# ProProject_stm32_motordrive_2024-05-07.net
KiCad netlist of a schematic drawn in EasyEDA Pro
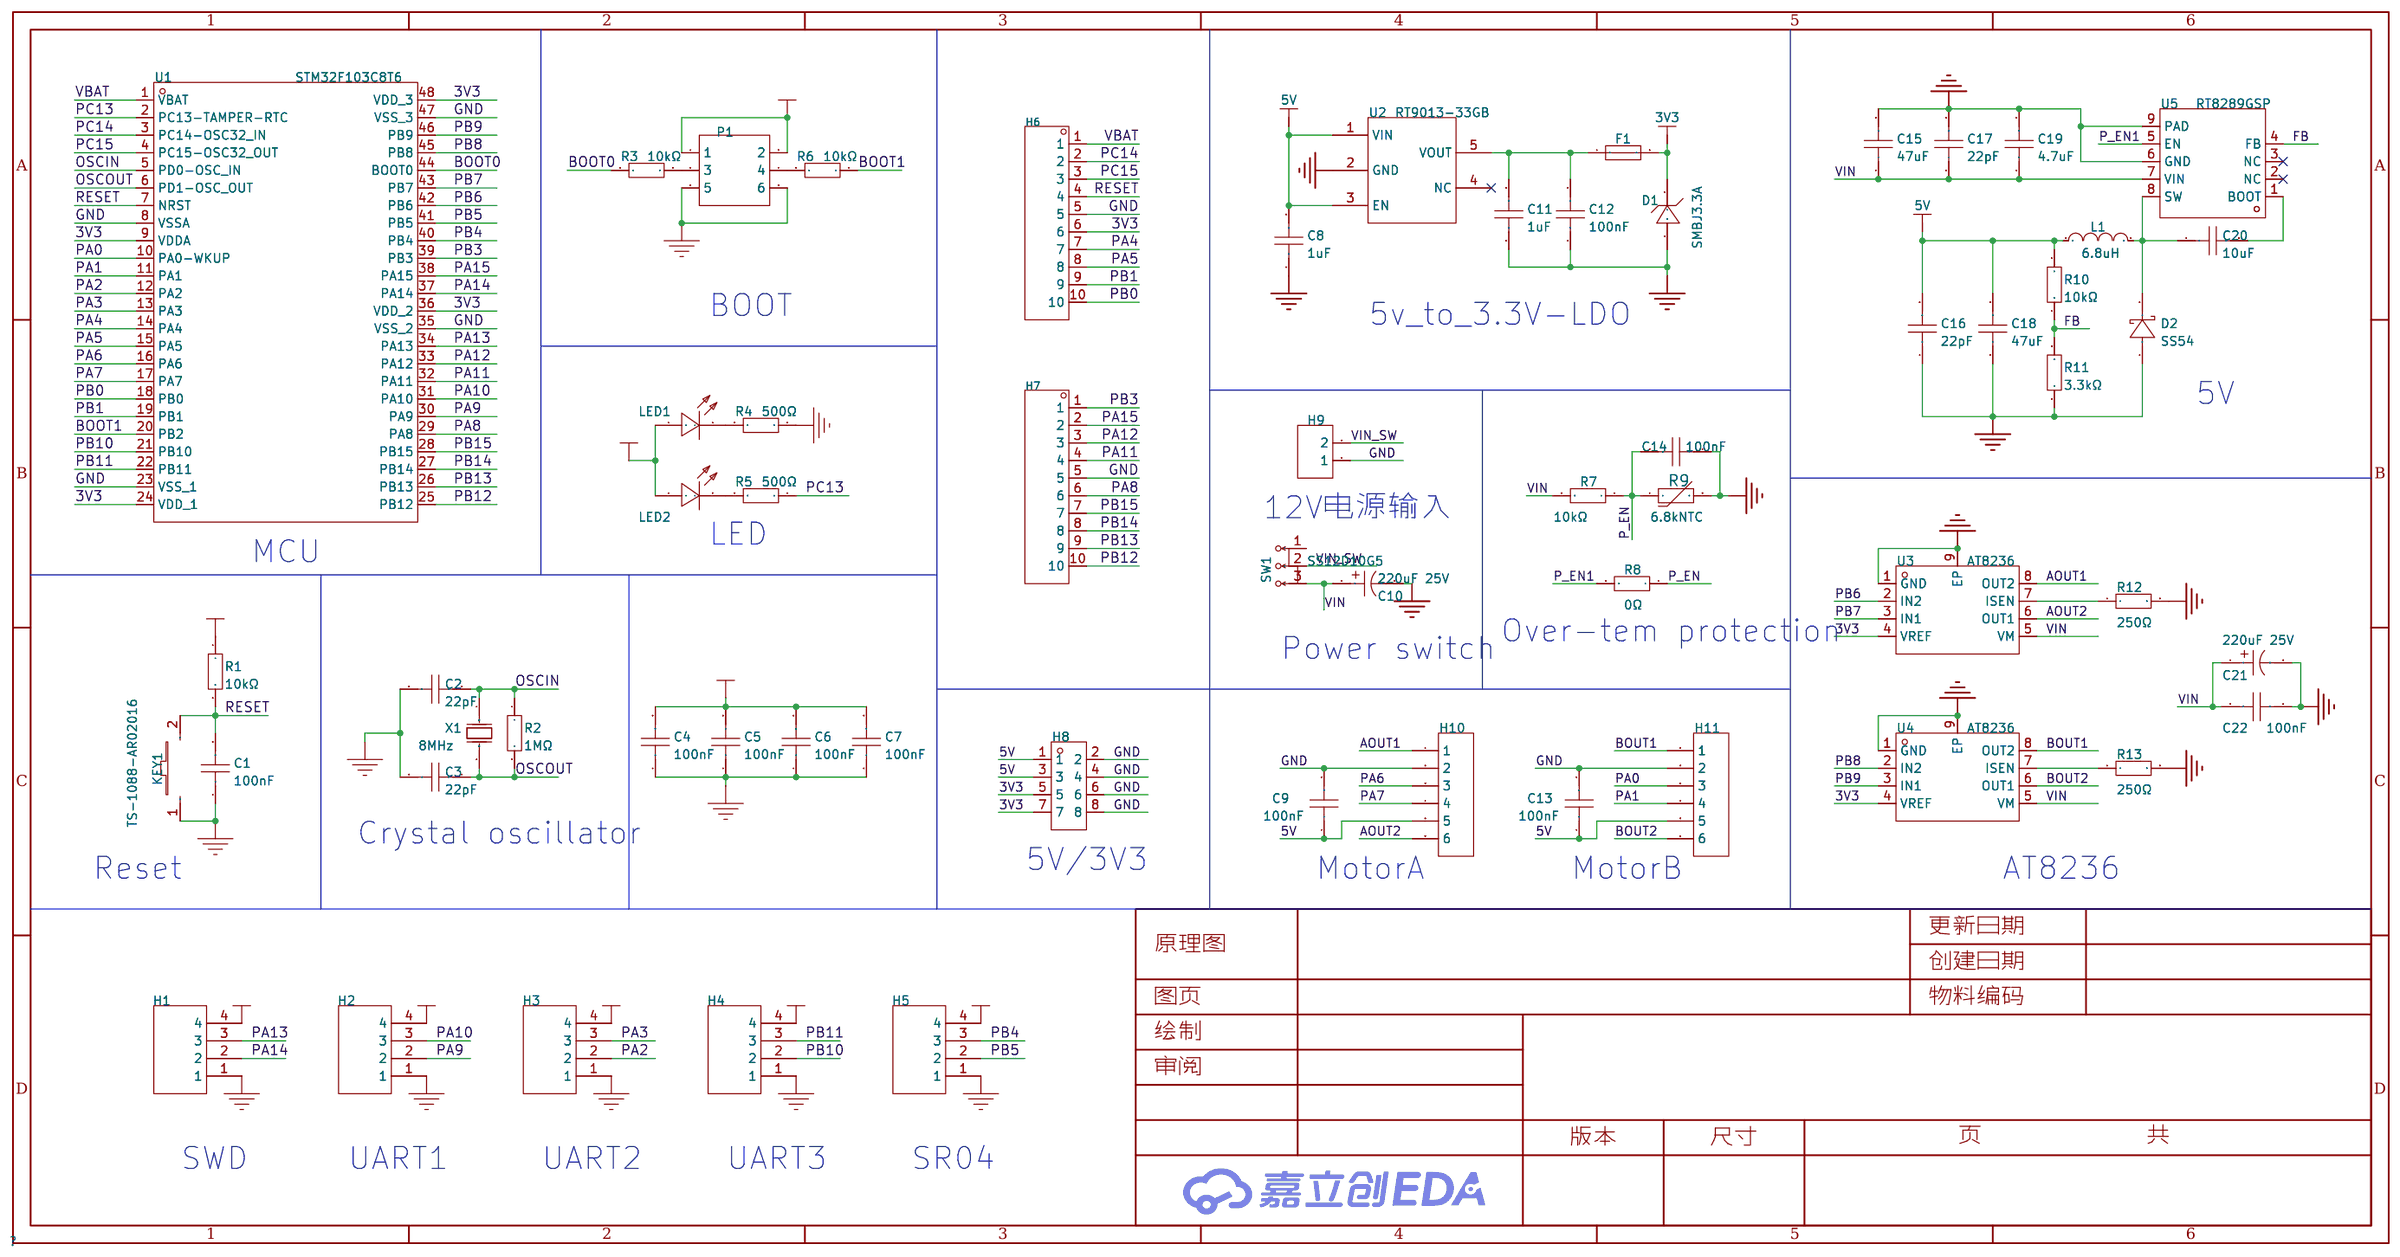
[diagram p0: schematic sheet]

(export (version "E")
  (design (tool "Eeschema 10.0.6"))
  (components
    (comp (ref "C1")
      (value "100nF")
      (fields
        (field (name "Manufacturer Part") "CC0603KRX7R9BB104")
        (field (name "Manufacturer") "YAGEO(国巨)")
      )
      (libsource (lib "easyedapro") (part "104"))
    )
    (comp (ref "C2")
      (value "22pF")
      (fields
        (field (name "Manufacturer Part") "CC0603JRNPO9BN220")
        (field (name "Manufacturer") "YAGEO(国巨)")
      )
      (libsource (lib "easyedapro") (part "22P"))
    )
    (comp (ref "C3")
      (value "22pF")
      (fields
        (field (name "Manufacturer Part") "CC0603JRNPO9BN220")
        (field (name "Manufacturer") "YAGEO(国巨)")
      )
      (libsource (lib "easyedapro") (part "22P"))
    )
    (comp (ref "C4")
      (value "100nF")
      (fields
        (field (name "Manufacturer Part") "CC0603KRX7R9BB104")
        (field (name "Manufacturer") "YAGEO(国巨)")
      )
      (libsource (lib "easyedapro") (part "104"))
    )
    (comp (ref "C5")
      (value "100nF")
      (fields
        (field (name "Manufacturer Part") "CC0603KRX7R9BB104")
        (field (name "Manufacturer") "YAGEO(国巨)")
      )
      (libsource (lib "easyedapro") (part "104"))
    )
    (comp (ref "C6")
      (value "100nF")
      (fields
        (field (name "Manufacturer Part") "CC0603KRX7R9BB104")
        (field (name "Manufacturer") "YAGEO(国巨)")
      )
      (libsource (lib "easyedapro") (part "104"))
    )
    (comp (ref "C7")
      (value "100nF")
      (fields
        (field (name "Manufacturer Part") "CC0603KRX7R9BB104")
        (field (name "Manufacturer") "YAGEO(国巨)")
      )
      (libsource (lib "easyedapro") (part "104"))
    )
    (comp (ref "C8")
      (value "1uF")
      (fields
        (field (name "Manufacturer Part") "CL10A105KB8NNNC")
        (field (name "Manufacturer") "SAMSUNG(三星)")
      )
      (libsource (lib "easyedapro") (part "CapAcitance"))
    )
    (comp (ref "C9")
      (value "100nF")
      (fields
        (field (name "Manufacturer Part") "CC0603KRX7R9BB104")
        (field (name "Manufacturer") "YAGEO(国巨)")
      )
      (libsource (lib "easyedapro") (part "CapAcitance"))
    )
    (comp (ref "C10")
      (value "220uF 25V")
      (footprint "easyedapro:CAP-SMD_BD6.3-L6.6-W6.6-LS7.2-FD")
      (description "容值:220uF;精度:±20%;额定电压:25V;纹波电流:165mA@120Hz;等效串联电阻:-;")
      (fields (field (name "Manufacturer Part") "RST220UF25V019") (field (name "Manufacturer") "KNSCHA(科尼盛)"))
      (libsource (lib "easyedapro") (part "RST220UF25V019"))
    )
    (comp (ref "C11")
      (value "1uF")
      (fields
        (field (name "Manufacturer Part") "CL10A105KB8NNNC")
        (field (name "Manufacturer") "SAMSUNG(三星)")
      )
      (libsource (lib "easyedapro") (part "CapAcitance"))
    )
    (comp (ref "C12")
      (value "100nF")
      (fields
        (field (name "Manufacturer Part") "CC0603KRX7R9BB104")
        (field (name "Manufacturer") "YAGEO(国巨)")
      )
      (libsource (lib "easyedapro") (part "CapAcitance"))
    )
    (comp (ref "C13")
      (value "100nF")
      (fields
        (field (name "Manufacturer Part") "CC0603KRX7R9BB104")
        (field (name "Manufacturer") "YAGEO(国巨)")
      )
      (libsource (lib "easyedapro") (part "CapAcitance"))
    )
    (comp (ref "C14")
      (value "100nF")
      (fields
        (field (name "Manufacturer Part") "CC0603KRX7R9BB104")
        (field (name "Manufacturer") "YAGEO(国巨)")
      )
      (libsource (lib "easyedapro") (part "CapAcitance"))
    )
    (comp (ref "C15")
      (value "47uF")
      (fields
        (field (name "Manufacturer Part") "CL10A476MQ8QRNC")
        (field (name "Manufacturer") "SAMSUNG(三星)")
      )
      (libsource (lib "easyedapro") (part "CapAcitance"))
    )
    (comp (ref "C16")
      (value "22pF")
      (fields
        (field (name "Manufacturer Part") "CC0603JRNPO9BN220")
        (field (name "Manufacturer") "YAGEO(国巨)")
      )
      (libsource (lib "easyedapro") (part "CapAcitance"))
    )
    (comp (ref "C17")
      (value "22pF")
      (fields
        (field (name "Manufacturer Part") "CC0603JRNPO9BN220")
        (field (name "Manufacturer") "YAGEO(国巨)")
      )
      (libsource (lib "easyedapro") (part "CapAcitance"))
    )
    (comp (ref "C18")
      (value "47uF")
      (fields
        (field (name "Manufacturer Part") "CL10A476MQ8QRNC")
        (field (name "Manufacturer") "SAMSUNG(三星)")
      )
      (libsource (lib "easyedapro") (part "CapAcitance"))
    )
    (comp (ref "C19")
      (value "4.7uF")
      (fields
        (field (name "Manufacturer Part") "CL10A475KP8NNNC")
        (field (name "Manufacturer") "SAMSUNG(三星)")
      )
      (libsource (lib "easyedapro") (part "CapAcitance"))
    )
    (comp (ref "C20")
      (value "10uF")
      (fields
        (field (name "Manufacturer Part") "CL10A106KP8NNNC")
        (field (name "Manufacturer") "SAMSUNG(三星)")
      )
      (libsource (lib "easyedapro") (part "CapAcitance"))
    )
    (comp (ref "C21")
      (value "220uF 25V")
      (footprint "easyedapro:CAP-SMD_BD6.3-L6.6-W6.6-LS7.2-FD")
      (description "容值:220uF;精度:±20%;额定电压:25V;纹波电流:165mA@120Hz;等效串联电阻:-;")
      (fields (field (name "Manufacturer Part") "RST220UF25V019") (field (name "Manufacturer") "KNSCHA(科尼盛)"))
      (libsource (lib "easyedapro") (part "RST220UF25V019"))
    )
    (comp (ref "C22")
      (value "100nF")
      (fields
        (field (name "Manufacturer Part") "CC0603KRX7R9BB104")
        (field (name "Manufacturer") "YAGEO(国巨)")
      )
      (libsource (lib "easyedapro") (part "CapAcitance"))
    )
    (comp (ref "D1")
      (value "SMBJ3.3A")
      (footprint "easyedapro:SMB_L4.6-W3.6-LS5.3-RD")
      (description "反向截止电压(Vrwm):3.3V;最大钳位电压:7.3V;峰值脉冲功率(Ppp)@10/1000us:600W;击穿电压:4.1V;")
      (fields (field (name "Manufacturer") "JKSEMI(金开盛)"))
      (libsource (lib "easyedapro") (part "SMBJ3.3A_C362089"))
    )
    (comp (ref "D2")
      (value "SS54")
      (footprint "easyedapro:SMA_L4.3-W2.6-LS5.0-FD")
      (description "二极管配置:独立式;正向压降(Vf):550mV@5.0A;直流反向耐压(Vr):40V;平均整流电流(Io):5A;")
      (fields (field (name "Manufacturer") "宏迦橙"))
      (libsource (lib "easyedapro") (part "SS54_C7420369"))
    )
    (comp (ref "F1")
      (value "BSMD0603-050-6V")
      (footprint "easyedapro:F0603")
      (description "最大电压:6V;最大电流:40A;保持电流:500mA;跳闸电流:1A;")
      (fields (field (name "Manufacturer") "BHFUSE(佰宏)"))
      (libsource (lib "easyedapro") (part "BSMD0603-050-6V"))
    )
    (comp (ref "H1")
      (value "PZ254V-11-04P")
      (fields (field (name "Manufacturer") "XFCN(兴飞)"))
      (libsource (lib "easyedapro") (part "220S-1*4P H=8.5MM Ytype Gold-plated"))
    )
    (comp (ref "H2")
      (value "PZ254V-11-04P")
      (fields (field (name "Manufacturer") "XFCN(兴飞)"))
      (libsource (lib "easyedapro") (part "220S-1*4P H=8.5MM Ytype Gold-plated"))
    )
    (comp (ref "H3")
      (value "PZ254V-11-04P")
      (fields (field (name "Manufacturer") "XFCN(兴飞)"))
      (libsource (lib "easyedapro") (part "220S-1*4P H=8.5MM Ytype Gold-plated"))
    )
    (comp (ref "H4")
      (value "PZ254V-11-04P")
      (fields (field (name "Manufacturer") "XFCN(兴飞)"))
      (libsource (lib "easyedapro") (part "220S-1*4P H=8.5MM Ytype Gold-plated"))
    )
    (comp (ref "H5")
      (value "PZ254V-11-04P")
      (fields (field (name "Manufacturer") "XFCN(兴飞)"))
      (libsource (lib "easyedapro") (part "220S-1*4P H=8.5MM Ytype Gold-plated"))
    )
    (comp (ref "H6")
      (value "2.54-1*10P针")
      (footprint "easyedapro:HDR-TH_10P-P2.54-V-M-1")
      (fields (field (name "Manufacturer") "BOOMELE(博穆精密)"))
      (libsource (lib "easyedapro") (part "Header-Male-2.54_1x10"))
    )
    (comp (ref "H7")
      (value "2.54-1*10P针")
      (footprint "easyedapro:HDR-TH_10P-P2.54-V-M-1")
      (fields (field (name "Manufacturer") "BOOMELE(博穆精密)"))
      (libsource (lib "easyedapro") (part "Header-Male-2.54_1x10"))
    )
    (comp (ref "H8")
      (value "PZ2.54-2*4")
      (footprint "easyedapro:HDR-TH_8P-P2.54-V-M-R2-C4-S2.54")
      (description "插针结构:2x4P;间距:2.54mm;排数:双排;总PIN位数:8P;")
      (fields (field (name "Manufacturer") "ZHOURI(洲日)"))
      (libsource (lib "easyedapro") (part "PZ2.54-2*4"))
    )
    (comp (ref "H9")
      (value "XY301V-A-5.0-2P")
      (fields (field (name "Manufacturer") "XINLAIYA(新莱亚)"))
      (libsource (lib "easyedapro") (part "Header-Female-2.54_1x2"))
    )
    (comp (ref "H10")
      (value "~")
      (footprint "easyedapro:XH2.54-LI-6P弯针")
      (libsource (lib "easyedapro") (part "XH2.54-LI-6P弯针"))
    )
    (comp (ref "H11")
      (value "~")
      (footprint "easyedapro:XH2.54-LI-6P弯针")
      (libsource (lib "easyedapro") (part "XH2.54-LI-6P弯针"))
    )
    (comp (ref "KEY1")
      (value "TS-1088-AR02016")
      (fields (field (name "Manufacturer") "XUNPU(讯普)"))
      (libsource (lib "easyedapro") (part "Switch3x4x2"))
    )
    (comp (ref "L1")
      (value "6.8uH")
      (fields (field (name "Manufacturer Part") "FXL0630-6R8-M") (field (name "Manufacturer") "cjiang(长江微电)"))
      (libsource (lib "easyedapro") (part "SDFL1608S100KTF"))
    )
    (comp (ref "LED1")
      (value "NCD0805R1")
      (fields (field (name "Manufacturer") "国星光电"))
      (libsource (lib "easyedapro") (part "204-10SURD/S530-A3"))
    )
    (comp (ref "LED2")
      (value "NCD0805R1")
      (fields (field (name "Manufacturer") "国星光电"))
      (libsource (lib "easyedapro") (part "204-10SURD/S530-A3"))
    )
    (comp (ref "P1")
      (value "2.54-2*3P针")
      (fields (field (name "Manufacturer") "BOOMELE(博穆精密)"))
      (libsource (lib "easyedapro") (part "HDR-IDC-2.54-2X3P"))
    )
    (comp (ref "R1")
      (value "10kΩ")
      (fields
        (field (name "Manufacturer Part") "0603WAF1002T5E")
        (field (name "Manufacturer") "UNI-ROYAL(厚声)")
      )
      (libsource (lib "easyedapro") (part "电阻"))
    )
    (comp (ref "R2")
      (value "1MΩ")
      (fields
        (field (name "Manufacturer Part") "0603WAF1004T5E")
        (field (name "Manufacturer") "UNI-ROYAL(厚声)")
      )
      (libsource (lib "easyedapro") (part "电阻"))
    )
    (comp (ref "R3")
      (value "10kΩ")
      (fields
        (field (name "Manufacturer Part") "0603WAF1002T5E")
        (field (name "Manufacturer") "UNI-ROYAL(厚声)")
      )
      (libsource (lib "easyedapro") (part "电阻"))
    )
    (comp (ref "R4")
      (value "500Ω")
      (fields (field (name "Manufacturer Part") "RT0603BRC07500RL") (field (name "Manufacturer") "YAGEO(国巨)"))
      (libsource (lib "easyedapro") (part "电阻"))
    )
    (comp (ref "R5")
      (value "500Ω")
      (fields (field (name "Manufacturer Part") "RT0603BRC07500RL") (field (name "Manufacturer") "YAGEO(国巨)"))
      (libsource (lib "easyedapro") (part "电阻"))
    )
    (comp (ref "R6")
      (value "10kΩ")
      (fields
        (field (name "Manufacturer Part") "0603WAF1002T5E")
        (field (name "Manufacturer") "UNI-ROYAL(厚声)")
      )
      (libsource (lib "easyedapro") (part "电阻"))
    )
    (comp (ref "R7")
      (value "10kΩ")
      (fields (field (name "Manufacturer Part") "RT0603BRD0710KL") (field (name "Manufacturer") "YAGEO(国巨)"))
      (libsource (lib "easyedapro") (part "电阻"))
    )
    (comp (ref "R8")
      (value "0Ω")
      (fields
        (field (name "Manufacturer Part") "0603WAF0000T5E")
        (field (name "Manufacturer") "UNI-ROYAL(厚声)")
      )
      (libsource (lib "easyedapro") (part "电阻"))
    )
    (comp (ref "R9")
      (value "6.8kNTC")
      (footprint "easyedapro:R0603")
      (description "阻值(25°C):6.8kΩ;B值(25°C/50°C):3950K;电阻精度:±5%;功率:100mW;B值精度:±3%;最大稳态电流(25°C):380uA;")
      (fields (field (name "Manufacturer") "muRata(村田)"))
      (libsource (lib "easyedapro") (part "NCP18XW682J03RB"))
    )
    (comp (ref "R10")
      (value "10kΩ")
      (fields (field (name "Manufacturer Part") "RT0603BRD0710KL") (field (name "Manufacturer") "YAGEO(国巨)"))
      (libsource (lib "easyedapro") (part "电阻"))
    )
    (comp (ref "R11")
      (value "3.3kΩ")
      (fields
        (field (name "Manufacturer Part") "0603WAF3301T5E")
        (field (name "Manufacturer") "UNI-ROYAL(厚声)")
      )
      (libsource (lib "easyedapro") (part "电阻"))
    )
    (comp (ref "R12")
      (value "250Ω")
      (fields (field (name "Manufacturer Part") "RT0603BRE07250RL") (field (name "Manufacturer") "YAGEO(国巨)"))
      (libsource (lib "easyedapro") (part "电阻"))
    )
    (comp (ref "R13")
      (value "250Ω")
      (fields (field (name "Manufacturer Part") "RT0603BRE07250RL") (field (name "Manufacturer") "YAGEO(国巨)"))
      (libsource (lib "easyedapro") (part "电阻"))
    )
    (comp (ref "SW1")
      (value "SS12D10G5")
      (fields (field (name "Manufacturer") "SHOU HAN(首韩)"))
      (libsource (lib "easyedapro") (part "3脚两档开关(SS12D10G4型号）"))
    )
    (comp (ref "U1")
      (value "STM32F103C8T6")
      (fields (field (name "Manufacturer") "ST(意法半导体)"))
      (libsource (lib "easyedapro") (part "STM32F103C8T6"))
    )
    (comp (ref "U2")
      (value "RT9013-33GB")
      (footprint "easyedapro:SOT-23-5_L3.0-W1.7-P0.95-LS2.8-BL")
      (description "输出类型:固定;最大输入电压:5.5V;输出电压:3.3V;最大输出电流:500mA;电源纹波抑制比(PSRR):50dB@(10kHz);输出极性:正极;")
      (fields (field (name "Manufacturer") "RICHTEK(立锜)"))
      (libsource (lib "easyedapro") (part "RT9013-33GB"))
    )
    (comp (ref "U3")
      (value "AT8236")
      (footprint "easyedapro:ESOP-8_L4.9-W3.9-P1.27-LS6.0-BL-EP")
      (fields (field (name "Manufacturer") "杭州中科微"))
      (libsource (lib "easyedapro") (part "AT8236"))
    )
    (comp (ref "U4")
      (value "AT8236")
      (footprint "easyedapro:ESOP-8_L4.9-W3.9-P1.27-LS6.0-BL-EP")
      (fields (field (name "Manufacturer") "杭州中科微"))
      (libsource (lib "easyedapro") (part "AT8236"))
    )
    (comp (ref "U5")
      (value "RT8289GSP")
      (footprint "easyedapro:SOIC-8_L5.0-W4.0-P1.27-LS6.0-BL-EP2.0")
      (description "功能类型:降压型;输出类型:可调;输入电压:5.5V~32V;输出电压:1.222V~26V;输出电流(最大值):5A;")
      (fields (field (name "Manufacturer") "RICHTEK(立锜)"))
      (libsource (lib "easyedapro") (part "RT8289GSP"))
    )
    (comp (ref "X1")
      (value "8MHz")
      (fields (field (name "Manufacturer Part") "X50328MSB2GI") (field (name "Manufacturer") "YXC(扬兴晶振)"))
      (libsource (lib "easyedapro") (part "8MHz"))
    )
  )
  (nets
    (net (code "1") (name "/AOUT1") (class "Default")
      (node (ref "H10") (pin "1") (pinfunction "1_1") (pintype "input"))
      (node (ref "U3") (pin "8") (pinfunction "OUT2_8") (pintype "unspecified"))
    )
    (net (code "2") (name "/AOUT2") (class "Default")
      (node (ref "H10") (pin "6") (pinfunction "6_6") (pintype "input"))
      (node (ref "U3") (pin "6") (pinfunction "OUT1_6") (pintype "unspecified"))
    )
    (net (code "3") (name "/BOOT0") (class "Default")
      (node (ref "R3") (pin "2") (pinfunction "2_2") (pintype "input"))
      (node (ref "U1") (pin "44") (pinfunction "BOOT0_44") (pintype "unspecified"))
    )
    (net (code "4") (name "/BOOT1") (class "Default")
      (node (ref "R6") (pin "1") (pinfunction "1_1") (pintype "input"))
      (node (ref "U1") (pin "20") (pinfunction "PB2_20") (pintype "unspecified"))
    )
    (net (code "5") (name "/BOUT1") (class "Default")
      (node (ref "H11") (pin "1") (pinfunction "1_1") (pintype "input"))
      (node (ref "U4") (pin "8") (pinfunction "OUT2_8") (pintype "unspecified"))
    )
    (net (code "6") (name "/BOUT2") (class "Default")
      (node (ref "H11") (pin "6") (pinfunction "6_6") (pintype "input"))
      (node (ref "U4") (pin "6") (pinfunction "OUT1_6") (pintype "unspecified"))
    )
    (net (code "7") (name "/FB") (class "Default")
      (node (ref "R10") (pin "1") (pinfunction "1_1") (pintype "input"))
      (node (ref "R11") (pin "2") (pinfunction "2_2") (pintype "input"))
      (node (ref "U5") (pin "4") (pinfunction "FB_4") (pintype "unspecified"))
    )
    (net (code "8") (name "/OSCIN") (class "Default")
      (node (ref "C2") (pin "1") (pinfunction "1_1") (pintype "unspecified"))
      (node (ref "R2") (pin "1") (pinfunction "1_1") (pintype "input"))
      (node (ref "U1") (pin "5") (pinfunction "PD0-OSC_IN_5") (pintype "unspecified"))
      (node (ref "X1") (pin "1") (pinfunction "OSC1_1") (pintype "unspecified"))
    )
    (net (code "9") (name "/OSCOUT") (class "Default")
      (node (ref "C3") (pin "1") (pinfunction "1_1") (pintype "unspecified"))
      (node (ref "R2") (pin "2") (pinfunction "2_2") (pintype "input"))
      (node (ref "U1") (pin "6") (pinfunction "PD1-OSC_OUT_6") (pintype "unspecified"))
      (node (ref "X1") (pin "2") (pinfunction "OSC2_2") (pintype "unspecified"))
    )
    (net (code "10") (name "/PA0") (class "Default")
      (node (ref "H11") (pin "3") (pinfunction "3_3") (pintype "input"))
      (node (ref "U1") (pin "10") (pinfunction "PA0-WKUP_10") (pintype "unspecified"))
    )
    (net (code "11") (name "/PA1") (class "Default")
      (node (ref "H11") (pin "4") (pinfunction "4_4") (pintype "input"))
      (node (ref "U1") (pin "11") (pinfunction "PA1_11") (pintype "unspecified"))
    )
    (net (code "12") (name "/PA2") (class "Default")
      (node (ref "H3") (pin "2") (pinfunction "2_2") (pintype "unspecified"))
      (node (ref "U1") (pin "12") (pinfunction "PA2_12") (pintype "unspecified"))
    )
    (net (code "13") (name "/PA3") (class "Default")
      (node (ref "H3") (pin "3") (pinfunction "3_3") (pintype "unspecified"))
      (node (ref "U1") (pin "13") (pinfunction "PA3_13") (pintype "unspecified"))
    )
    (net (code "14") (name "/PA4") (class "Default")
      (node (ref "H6") (pin "7") (pinfunction "7_7") (pintype "input"))
      (node (ref "U1") (pin "14") (pinfunction "PA4_14") (pintype "unspecified"))
    )
    (net (code "15") (name "/PA5") (class "Default")
      (node (ref "H6") (pin "8") (pinfunction "8_8") (pintype "input"))
      (node (ref "U1") (pin "15") (pinfunction "PA5_15") (pintype "unspecified"))
    )
    (net (code "16") (name "/PA6") (class "Default")
      (node (ref "H10") (pin "3") (pinfunction "3_3") (pintype "input"))
      (node (ref "U1") (pin "16") (pinfunction "PA6_16") (pintype "unspecified"))
    )
    (net (code "17") (name "/PA7") (class "Default")
      (node (ref "H10") (pin "4") (pinfunction "4_4") (pintype "input"))
      (node (ref "U1") (pin "17") (pinfunction "PA7_17") (pintype "unspecified"))
    )
    (net (code "18") (name "/PA8") (class "Default")
      (node (ref "H7") (pin "6") (pinfunction "6_6") (pintype "input"))
      (node (ref "U1") (pin "29") (pinfunction "PA8_29") (pintype "unspecified"))
    )
    (net (code "19") (name "/PA9") (class "Default")
      (node (ref "H2") (pin "2") (pinfunction "2_2") (pintype "unspecified"))
      (node (ref "U1") (pin "30") (pinfunction "PA9_30") (pintype "unspecified"))
    )
    (net (code "20") (name "/PA10") (class "Default")
      (node (ref "H2") (pin "3") (pinfunction "3_3") (pintype "unspecified"))
      (node (ref "U1") (pin "31") (pinfunction "PA10_31") (pintype "unspecified"))
    )
    (net (code "21") (name "/PA11") (class "Default")
      (node (ref "H7") (pin "4") (pinfunction "4_4") (pintype "input"))
      (node (ref "U1") (pin "32") (pinfunction "PA11_32") (pintype "unspecified"))
    )
    (net (code "22") (name "/PA12") (class "Default")
      (node (ref "H7") (pin "3") (pinfunction "3_3") (pintype "input"))
      (node (ref "U1") (pin "33") (pinfunction "PA12_33") (pintype "unspecified"))
    )
    (net (code "23") (name "/PA13") (class "Default")
      (node (ref "H1") (pin "3") (pinfunction "3_3") (pintype "unspecified"))
      (node (ref "U1") (pin "34") (pinfunction "PA13_34") (pintype "unspecified"))
    )
    (net (code "24") (name "/PA14") (class "Default")
      (node (ref "H1") (pin "2") (pinfunction "2_2") (pintype "unspecified"))
      (node (ref "U1") (pin "37") (pinfunction "PA14_37") (pintype "unspecified"))
    )
    (net (code "25") (name "/PA15") (class "Default")
      (node (ref "H7") (pin "2") (pinfunction "2_2") (pintype "input"))
      (node (ref "U1") (pin "38") (pinfunction "PA15_38") (pintype "unspecified"))
    )
    (net (code "26") (name "/PB0") (class "Default")
      (node (ref "H6") (pin "10") (pinfunction "10_10") (pintype "input"))
      (node (ref "U1") (pin "18") (pinfunction "PB0_18") (pintype "unspecified"))
    )
    (net (code "27") (name "/PB1") (class "Default")
      (node (ref "H6") (pin "9") (pinfunction "9_9") (pintype "input"))
      (node (ref "U1") (pin "19") (pinfunction "PB1_19") (pintype "unspecified"))
    )
    (net (code "28") (name "/PB3") (class "Default")
      (node (ref "H7") (pin "1") (pinfunction "1_1") (pintype "input"))
      (node (ref "U1") (pin "39") (pinfunction "PB3_39") (pintype "unspecified"))
    )
    (net (code "29") (name "/PB4") (class "Default")
      (node (ref "H5") (pin "3") (pinfunction "3_3") (pintype "unspecified"))
      (node (ref "U1") (pin "40") (pinfunction "PB4_40") (pintype "unspecified"))
    )
    (net (code "30") (name "/PB5") (class "Default")
      (node (ref "H5") (pin "2") (pinfunction "2_2") (pintype "unspecified"))
      (node (ref "U1") (pin "41") (pinfunction "PB5_41") (pintype "unspecified"))
    )
    (net (code "31") (name "/PB6") (class "Default")
      (node (ref "U1") (pin "42") (pinfunction "PB6_42") (pintype "unspecified"))
      (node (ref "U3") (pin "2") (pinfunction "IN2_2") (pintype "unspecified"))
    )
    (net (code "32") (name "/PB7") (class "Default")
      (node (ref "U1") (pin "43") (pinfunction "PB7_43") (pintype "unspecified"))
      (node (ref "U3") (pin "3") (pinfunction "IN1_3") (pintype "unspecified"))
    )
    (net (code "33") (name "/PB8") (class "Default")
      (node (ref "U1") (pin "45") (pinfunction "PB8_45") (pintype "unspecified"))
      (node (ref "U4") (pin "2") (pinfunction "IN2_2") (pintype "unspecified"))
    )
    (net (code "34") (name "/PB9") (class "Default")
      (node (ref "U1") (pin "46") (pinfunction "PB9_46") (pintype "unspecified"))
      (node (ref "U4") (pin "3") (pinfunction "IN1_3") (pintype "unspecified"))
    )
    (net (code "35") (name "/PB10") (class "Default")
      (node (ref "H4") (pin "2") (pinfunction "2_2") (pintype "unspecified"))
      (node (ref "U1") (pin "21") (pinfunction "PB10_21") (pintype "unspecified"))
    )
    (net (code "36") (name "/PB11") (class "Default")
      (node (ref "H4") (pin "3") (pinfunction "3_3") (pintype "unspecified"))
      (node (ref "U1") (pin "22") (pinfunction "PB11_22") (pintype "unspecified"))
    )
    (net (code "37") (name "/PB12") (class "Default")
      (node (ref "H7") (pin "10") (pinfunction "10_10") (pintype "input"))
      (node (ref "U1") (pin "25") (pinfunction "PB12_25") (pintype "unspecified"))
    )
    (net (code "38") (name "/PB13") (class "Default")
      (node (ref "H7") (pin "9") (pinfunction "9_9") (pintype "input"))
      (node (ref "U1") (pin "26") (pinfunction "PB13_26") (pintype "unspecified"))
    )
    (net (code "39") (name "/PB14") (class "Default")
      (node (ref "H7") (pin "8") (pinfunction "8_8") (pintype "input"))
      (node (ref "U1") (pin "27") (pinfunction "PB14_27") (pintype "unspecified"))
    )
    (net (code "40") (name "/PB15") (class "Default")
      (node (ref "H7") (pin "7") (pinfunction "7_7") (pintype "input"))
      (node (ref "U1") (pin "28") (pinfunction "PB15_28") (pintype "unspecified"))
    )
    (net (code "41") (name "/PC13") (class "Default")
      (node (ref "R5") (pin "1") (pinfunction "1_1") (pintype "input"))
      (node (ref "U1") (pin "2") (pinfunction "PC13-TAMPER-RTC_2") (pintype "unspecified"))
    )
    (net (code "42") (name "/PC14") (class "Default")
      (node (ref "H6") (pin "2") (pinfunction "2_2") (pintype "input"))
      (node (ref "U1") (pin "3") (pinfunction "PC14-OSC32_IN_3") (pintype "unspecified"))
    )
    (net (code "43") (name "/PC15") (class "Default")
      (node (ref "H6") (pin "3") (pinfunction "3_3") (pintype "input"))
      (node (ref "U1") (pin "4") (pinfunction "PC15-OSC32_OUT_4") (pintype "unspecified"))
    )
    (net (code "44") (name "/P_EN") (class "Default")
      (node (ref "C14") (pin "2") (pinfunction "2_2") (pintype "input"))
      (node (ref "R7") (pin "1") (pinfunction "1_1") (pintype "input"))
      (node (ref "R8") (pin "1") (pinfunction "1_1") (pintype "input"))
      (node (ref "R9") (pin "1") (pinfunction "1_1") (pintype "input"))
    )
    (net (code "45") (name "/P_EN1") (class "Default")
      (node (ref "R8") (pin "2") (pinfunction "2_2") (pintype "input"))
      (node (ref "U5") (pin "5") (pinfunction "EN_5") (pintype "unspecified"))
    )
    (net (code "46") (name "/RESET") (class "Default")
      (node (ref "C1") (pin "2") (pinfunction "2_2") (pintype "unspecified"))
      (node (ref "H6") (pin "4") (pinfunction "4_4") (pintype "input"))
      (node (ref "KEY1") (pin "2") (pinfunction "2_2") (pintype "unspecified"))
      (node (ref "R1") (pin "2") (pinfunction "2_2") (pintype "input"))
      (node (ref "U1") (pin "7") (pinfunction "NRST_7") (pintype "unspecified"))
    )
    (net (code "47") (name "/VBAT") (class "Default")
      (node (ref "H6") (pin "1") (pinfunction "1_1") (pintype "input"))
      (node (ref "U1") (pin "1") (pinfunction "VBAT_1") (pintype "unspecified"))
    )
    (net (code "48") (name "/VIN") (class "Default")
      (node (ref "C10") (pin "1") (pinfunction "1_1") (pintype "input"))
      (node (ref "C15") (pin "1") (pinfunction "1_1") (pintype "input"))
      (node (ref "C17") (pin "1") (pinfunction "1_1") (pintype "input"))
      (node (ref "C19") (pin "1") (pinfunction "1_1") (pintype "input"))
      (node (ref "C21") (pin "1") (pinfunction "1_1") (pintype "input"))
      (node (ref "C22") (pin "2") (pinfunction "2_2") (pintype "input"))
      (node (ref "R7") (pin "2") (pinfunction "2_2") (pintype "input"))
      (node (ref "SW1") (pin "3") (pinfunction "3_3") (pintype "input"))
      (node (ref "U3") (pin "5") (pinfunction "VM_5") (pintype "unspecified"))
      (node (ref "U4") (pin "5") (pinfunction "VM_5") (pintype "unspecified"))
      (node (ref "U5") (pin "7") (pinfunction "VIN_7") (pintype "unspecified"))
    )
    (net (code "49") (name "/VIN_SW") (class "Default")
      (node (ref "H9") (pin "2") (pinfunction "2_2") (pintype "input"))
      (node (ref "SW1") (pin "2") (pinfunction "2_2") (pintype "input"))
    )
    (net (code "50") (name "3V3") (class "Default")
      (node (ref "C4") (pin "2") (pinfunction "2_2") (pintype "unspecified"))
      (node (ref "C5") (pin "2") (pinfunction "2_2") (pintype "unspecified"))
      (node (ref "C6") (pin "2") (pinfunction "2_2") (pintype "unspecified"))
      (node (ref "C7") (pin "2") (pinfunction "2_2") (pintype "unspecified"))
      (node (ref "D1") (pin "1") (pinfunction "1_1") (pintype "input"))
      (node (ref "F1") (pin "2") (pinfunction "2_2") (pintype "unspecified"))
      (node (ref "H6") (pin "6") (pinfunction "6_6") (pintype "input"))
      (node (ref "H8") (pin "5") (pinfunction "5_5") (pintype "unspecified"))
      (node (ref "H8") (pin "7") (pinfunction "7_7") (pintype "unspecified"))
      (node (ref "LED1") (pin "1") (pinfunction "A_1") (pintype "unspecified"))
      (node (ref "LED2") (pin "1") (pinfunction "A_1") (pintype "unspecified"))
      (node (ref "P1") (pin "1") (pinfunction "1_1") (pintype "unspecified"))
      (node (ref "P1") (pin "2") (pinfunction "2_2") (pintype "unspecified"))
      (node (ref "R1") (pin "1") (pinfunction "1_1") (pintype "input"))
      (node (ref "U1") (pin "24") (pinfunction "VDD_1_24") (pintype "unspecified"))
      (node (ref "U1") (pin "36") (pinfunction "VDD_2_36") (pintype "unspecified"))
      (node (ref "U1") (pin "48") (pinfunction "VDD_3_48") (pintype "unspecified"))
      (node (ref "U1") (pin "9") (pinfunction "VDDA_9") (pintype "unspecified"))
      (node (ref "U3") (pin "4") (pinfunction "VREF_4") (pintype "unspecified"))
      (node (ref "U4") (pin "4") (pinfunction "VREF_4") (pintype "unspecified"))
    )
    (net (code "51") (name "5V") (class "Default")
      (node (ref "C13") (pin "1") (pinfunction "1_1") (pintype "input"))
      (node (ref "C16") (pin "2") (pinfunction "2_2") (pintype "input"))
      (node (ref "C18") (pin "2") (pinfunction "2_2") (pintype "input"))
      (node (ref "C8") (pin "2") (pinfunction "2_2") (pintype "input"))
      (node (ref "C9") (pin "1") (pinfunction "1_1") (pintype "input"))
      (node (ref "H1") (pin "4") (pinfunction "4_4") (pintype "unspecified"))
      (node (ref "H10") (pin "5") (pinfunction "5_5") (pintype "input"))
      (node (ref "H11") (pin "5") (pinfunction "5_5") (pintype "input"))
      (node (ref "H2") (pin "4") (pinfunction "4_4") (pintype "unspecified"))
      (node (ref "H3") (pin "4") (pinfunction "4_4") (pintype "unspecified"))
      (node (ref "H4") (pin "4") (pinfunction "4_4") (pintype "unspecified"))
      (node (ref "H5") (pin "4") (pinfunction "4_4") (pintype "unspecified"))
      (node (ref "H8") (pin "1") (pinfunction "1_1") (pintype "unspecified"))
      (node (ref "H8") (pin "3") (pinfunction "3_3") (pintype "unspecified"))
      (node (ref "L1") (pin "1") (pinfunction "1_1") (pintype "unspecified"))
      (node (ref "R10") (pin "2") (pinfunction "2_2") (pintype "input"))
      (node (ref "U2") (pin "1") (pinfunction "VIN_1") (pintype "unspecified"))
      (node (ref "U2") (pin "3") (pinfunction "EN_3") (pintype "unspecified"))
    )
    (net (code "52") (name "GND") (class "Default")
      (node (ref "C1") (pin "1") (pinfunction "1_1") (pintype "unspecified"))
      (node (ref "C10") (pin "2") (pinfunction "2_2") (pintype "input"))
      (node (ref "C11") (pin "1") (pinfunction "1_1") (pintype "input"))
      (node (ref "C12") (pin "1") (pinfunction "1_1") (pintype "input"))
      (node (ref "C13") (pin "2") (pinfunction "2_2") (pintype "input"))
      (node (ref "C14") (pin "1") (pinfunction "1_1") (pintype "input"))
      (node (ref "C15") (pin "2") (pinfunction "2_2") (pintype "input"))
      (node (ref "C16") (pin "1") (pinfunction "1_1") (pintype "input"))
      (node (ref "C17") (pin "2") (pinfunction "2_2") (pintype "input"))
      (node (ref "C18") (pin "1") (pinfunction "1_1") (pintype "input"))
      (node (ref "C19") (pin "2") (pinfunction "2_2") (pintype "input"))
      (node (ref "C2") (pin "2") (pinfunction "2_2") (pintype "unspecified"))
      (node (ref "C21") (pin "2") (pinfunction "2_2") (pintype "input"))
      (node (ref "C22") (pin "1") (pinfunction "1_1") (pintype "input"))
      (node (ref "C3") (pin "2") (pinfunction "2_2") (pintype "unspecified"))
      (node (ref "C4") (pin "1") (pinfunction "1_1") (pintype "unspecified"))
      (node (ref "C5") (pin "1") (pinfunction "1_1") (pintype "unspecified"))
      (node (ref "C6") (pin "1") (pinfunction "1_1") (pintype "unspecified"))
      (node (ref "C7") (pin "1") (pinfunction "1_1") (pintype "unspecified"))
      (node (ref "C8") (pin "1") (pinfunction "1_1") (pintype "input"))
      (node (ref "C9") (pin "2") (pinfunction "2_2") (pintype "input"))
      (node (ref "D1") (pin "2") (pinfunction "2_2") (pintype "input"))
      (node (ref "D2") (pin "1") (pinfunction "A_1") (pintype "unspecified"))
      (node (ref "H1") (pin "1") (pinfunction "1_1") (pintype "unspecified"))
      (node (ref "H10") (pin "2") (pinfunction "2_2") (pintype "input"))
      (node (ref "H11") (pin "2") (pinfunction "2_2") (pintype "input"))
      (node (ref "H2") (pin "1") (pinfunction "1_1") (pintype "unspecified"))
      (node (ref "H3") (pin "1") (pinfunction "1_1") (pintype "unspecified"))
      (node (ref "H4") (pin "1") (pinfunction "1_1") (pintype "unspecified"))
      (node (ref "H5") (pin "1") (pinfunction "1_1") (pintype "unspecified"))
      (node (ref "H6") (pin "5") (pinfunction "5_5") (pintype "input"))
      (node (ref "H7") (pin "5") (pinfunction "5_5") (pintype "input"))
      (node (ref "H8") (pin "2") (pinfunction "2_2") (pintype "unspecified"))
      (node (ref "H8") (pin "4") (pinfunction "4_4") (pintype "unspecified"))
      (node (ref "H8") (pin "6") (pinfunction "6_6") (pintype "unspecified"))
      (node (ref "H8") (pin "8") (pinfunction "8_8") (pintype "unspecified"))
      (node (ref "H9") (pin "1") (pinfunction "1_1") (pintype "input"))
      (node (ref "KEY1") (pin "1") (pinfunction "1_1") (pintype "unspecified"))
      (node (ref "P1") (pin "5") (pinfunction "5_5") (pintype "unspecified"))
      (node (ref "P1") (pin "6") (pinfunction "6_6") (pintype "unspecified"))
      (node (ref "R11") (pin "1") (pinfunction "1_1") (pintype "input"))
      (node (ref "R12") (pin "2") (pinfunction "2_2") (pintype "input"))
      (node (ref "R13") (pin "2") (pinfunction "2_2") (pintype "input"))
      (node (ref "R4") (pin "1") (pinfunction "1_1") (pintype "input"))
      (node (ref "R9") (pin "2") (pinfunction "2_2") (pintype "input"))
      (node (ref "U1") (pin "23") (pinfunction "VSS_1_23") (pintype "unspecified"))
      (node (ref "U1") (pin "35") (pinfunction "VSS_2_35") (pintype "unspecified"))
      (node (ref "U1") (pin "47") (pinfunction "VSS_3_47") (pintype "unspecified"))
      (node (ref "U1") (pin "8") (pinfunction "VSSA_8") (pintype "unspecified"))
      (node (ref "U2") (pin "2") (pinfunction "GND_2") (pintype "unspecified"))
      (node (ref "U3") (pin "1") (pinfunction "GND_1") (pintype "unspecified"))
      (node (ref "U3") (pin "9") (pinfunction "EP_9") (pintype "unspecified"))
      (node (ref "U4") (pin "1") (pinfunction "GND_1") (pintype "unspecified"))
      (node (ref "U4") (pin "9") (pinfunction "EP_9") (pintype "unspecified"))
      (node (ref "U5") (pin "6") (pinfunction "GND_6") (pintype "unspecified"))
      (node (ref "U5") (pin "9") (pinfunction "PAD_9") (pintype "unspecified"))
    )
    (net (code "53") (name "Net-(D2-K)") (class "Default")
      (node (ref "C20") (pin "1") (pinfunction "1_1") (pintype "input"))
      (node (ref "D2") (pin "2") (pinfunction "K_2") (pintype "unspecified"))
      (node (ref "L1") (pin "2") (pinfunction "2_2") (pintype "unspecified"))
      (node (ref "U5") (pin "8") (pinfunction "SW_8") (pintype "unspecified"))
    )
    (net (code "54") (name "Net-(LED1-K)") (class "Default")
      (node (ref "LED1") (pin "2") (pinfunction "K_2") (pintype "unspecified"))
      (node (ref "R4") (pin "2") (pinfunction "2_2") (pintype "input"))
    )
    (net (code "55") (name "Net-(LED2-K)") (class "Default")
      (node (ref "LED2") (pin "2") (pinfunction "K_2") (pintype "unspecified"))
      (node (ref "R5") (pin "2") (pinfunction "2_2") (pintype "input"))
    )
    (net (code "56") (name "Net-(P1-Pad3)") (class "Default")
      (node (ref "P1") (pin "3") (pinfunction "3_3") (pintype "unspecified"))
      (node (ref "R3") (pin "1") (pinfunction "1_1") (pintype "input"))
    )
    (net (code "57") (name "Net-(P1-Pad4)") (class "Default")
      (node (ref "P1") (pin "4") (pinfunction "4_4") (pintype "unspecified"))
      (node (ref "R6") (pin "2") (pinfunction "2_2") (pintype "input"))
    )
    (net (code "58") (name "Net-(U2-VOUT)") (class "Default")
      (node (ref "C11") (pin "2") (pinfunction "2_2") (pintype "input"))
      (node (ref "C12") (pin "2") (pinfunction "2_2") (pintype "input"))
      (node (ref "F1") (pin "1") (pinfunction "1_1") (pintype "unspecified"))
      (node (ref "U2") (pin "5") (pinfunction "VOUT_5") (pintype "unspecified"))
    )
    (net (code "59") (name "Net-(U3-ISEN)") (class "Default")
      (node (ref "R12") (pin "1") (pinfunction "1_1") (pintype "input"))
      (node (ref "U3") (pin "7") (pinfunction "ISEN_7") (pintype "unspecified"))
    )
    (net (code "60") (name "Net-(U4-ISEN)") (class "Default")
      (node (ref "R13") (pin "1") (pinfunction "1_1") (pintype "input"))
      (node (ref "U4") (pin "7") (pinfunction "ISEN_7") (pintype "unspecified"))
    )
    (net (code "61") (name "Net-(U5-BOOT)") (class "Default")
      (node (ref "C20") (pin "2") (pinfunction "2_2") (pintype "input"))
      (node (ref "U5") (pin "1") (pinfunction "BOOT_1") (pintype "unspecified"))
    )
    (net (code "62") (name "unconnected-(SW1-Pad1)") (class "Default")
      (node (ref "SW1") (pin "1") (pinfunction "1_1") (pintype "input"))
    )
    (net (code "63") (name "unconnected-(U2-NC-Pad4)") (class "Default")
      (node (ref "U2") (pin "4") (pinfunction "NC_4") (pintype "unspecified+no_connect"))
    )
    (net (code "64") (name "unconnected-(U5-NC-Pad2)") (class "Default")
      (node (ref "U5") (pin "2") (pinfunction "NC_2") (pintype "unspecified+no_connect"))
    )
    (net (code "65") (name "unconnected-(U5-NC-Pad3)") (class "Default")
      (node (ref "U5") (pin "3") (pinfunction "NC_3") (pintype "unspecified+no_connect"))
    )
  )
)
